# 10-Buffer.net
KiCad netlist of a schematic drawn in Altium Designer
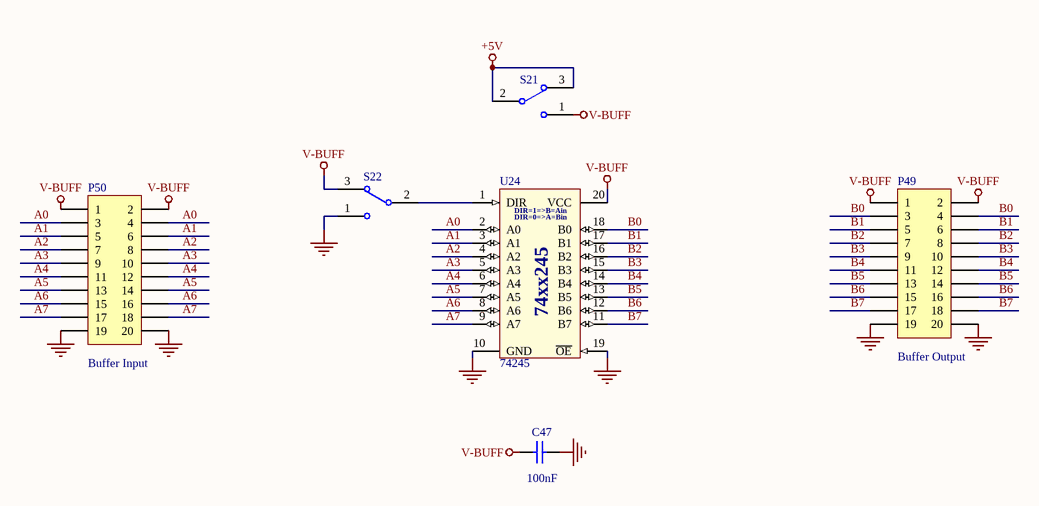
[diagram p0: 10-Buffer.SchDoc]

(export (version "E")
  (design (tool "Eeschema 10.0.6"))
  (components
    (comp (ref "C47")
      (value "100nF")
      (footprint "C-0805")
      (description "Capacitor")
      (fields (field (name "Comment") "104") (field (name "PUBLISHER") "Altium Limited"))
      (libsource (lib "Miscellaneous Devices") (part "Cap"))
    )
    (comp (ref "P49")
      (value "Buffer Output")
      (footprint "HDR2X10")
      (description "Header, 10-Pin, Dual row")
      (fields (field (name "Comment") "H10X2"))
      (libsource (lib "Miscellaneous Connectors") (part "Header 10X2"))
    )
    (comp (ref "P50")
      (value "Buffer Input")
      (footprint "HDR2X10")
      (description "Header, 10-Pin, Dual row")
      (fields (field (name "Comment") "H10X2"))
      (libsource (lib "Miscellaneous Connectors") (part "Header 10X2"))
    )
    (comp (ref "S21")
      (value "SW-SPDT")
      (footprint "SW-DIP1SMD")
      (description "SPDT Subminiature Toggle Switch, Right Angle Mounting, Vertical Actuation")
      (fields (field (name "PUBLISHER") "Altium Limited"))
      (libsource (lib "Miscellaneous Devices") (part "SW-SPDT"))
    )
    (comp (ref "S22")
      (value "SW-SPDT")
      (footprint "SW-DIP1SMD")
      (description "SPDT Subminiature Toggle Switch, Right Angle Mounting, Vertical Actuation")
      (fields (field (name "PUBLISHER") "Altium Limited"))
      (libsource (lib "Miscellaneous Devices") (part "SW-SPDT"))
    )
    (comp (ref "U24")
      (value "74245")
      (footprint "DIP20/W0.3")
      (description "Octal bus tranceiver; 3-state")
      (fields (field (name "COPYRIGHT BY") "VanDungEvn@gmail.com"))
      (libsource (lib "nhoccon1") (part "74245"))
    )
  )
  (nets
    (net (code "1") (name "+5V") (class "Default")
      (node (ref "S21") (pin "2") (pinfunction "2_2") (pintype "passive"))
      (node (ref "S21") (pin "3") (pinfunction "3_3") (pintype "passive"))
    )
    (net (code "2") (name "/A0") (class "Default")
      (node (ref "P50") (pin "3") (pinfunction "3_3") (pintype "passive"))
      (node (ref "P50") (pin "4") (pinfunction "4_4") (pintype "passive"))
      (node (ref "U24") (pin "2") (pinfunction "A0_2") (pintype "bidirectional"))
    )
    (net (code "3") (name "/A1") (class "Default")
      (node (ref "P50") (pin "5") (pinfunction "5_5") (pintype "passive"))
      (node (ref "P50") (pin "6") (pinfunction "6_6") (pintype "passive"))
      (node (ref "U24") (pin "3") (pinfunction "A1_3") (pintype "bidirectional"))
    )
    (net (code "4") (name "/A2") (class "Default")
      (node (ref "P50") (pin "7") (pinfunction "7_7") (pintype "passive"))
      (node (ref "P50") (pin "8") (pinfunction "8_8") (pintype "passive"))
      (node (ref "U24") (pin "4") (pinfunction "A2_4") (pintype "bidirectional"))
    )
    (net (code "5") (name "/A3") (class "Default")
      (node (ref "P50") (pin "10") (pinfunction "10_10") (pintype "passive"))
      (node (ref "P50") (pin "9") (pinfunction "9_9") (pintype "passive"))
      (node (ref "U24") (pin "5") (pinfunction "A3_5") (pintype "bidirectional"))
    )
    (net (code "6") (name "/A4") (class "Default")
      (node (ref "P50") (pin "11") (pinfunction "11_11") (pintype "passive"))
      (node (ref "P50") (pin "12") (pinfunction "12_12") (pintype "passive"))
      (node (ref "U24") (pin "6") (pinfunction "A4_6") (pintype "bidirectional"))
    )
    (net (code "7") (name "/A5") (class "Default")
      (node (ref "P50") (pin "13") (pinfunction "13_13") (pintype "passive"))
      (node (ref "P50") (pin "14") (pinfunction "14_14") (pintype "passive"))
      (node (ref "U24") (pin "7") (pinfunction "A5_7") (pintype "bidirectional"))
    )
    (net (code "8") (name "/A6") (class "Default")
      (node (ref "P50") (pin "15") (pinfunction "15_15") (pintype "passive"))
      (node (ref "P50") (pin "16") (pinfunction "16_16") (pintype "passive"))
      (node (ref "U24") (pin "8") (pinfunction "A6_8") (pintype "bidirectional"))
    )
    (net (code "9") (name "/A7") (class "Default")
      (node (ref "P50") (pin "17") (pinfunction "17_17") (pintype "passive"))
      (node (ref "P50") (pin "18") (pinfunction "18_18") (pintype "passive"))
      (node (ref "U24") (pin "9") (pinfunction "A7_9") (pintype "bidirectional"))
    )
    (net (code "10") (name "/B0") (class "Default")
      (node (ref "P49") (pin "3") (pinfunction "3_3") (pintype "passive"))
      (node (ref "P49") (pin "4") (pinfunction "4_4") (pintype "passive"))
      (node (ref "U24") (pin "18") (pinfunction "B0_18") (pintype "bidirectional"))
    )
    (net (code "11") (name "/B1") (class "Default")
      (node (ref "P49") (pin "5") (pinfunction "5_5") (pintype "passive"))
      (node (ref "P49") (pin "6") (pinfunction "6_6") (pintype "passive"))
      (node (ref "U24") (pin "17") (pinfunction "B1_17") (pintype "bidirectional"))
    )
    (net (code "12") (name "/B2") (class "Default")
      (node (ref "P49") (pin "7") (pinfunction "7_7") (pintype "passive"))
      (node (ref "P49") (pin "8") (pinfunction "8_8") (pintype "passive"))
      (node (ref "U24") (pin "16") (pinfunction "B2_16") (pintype "bidirectional"))
    )
    (net (code "13") (name "/B3") (class "Default")
      (node (ref "P49") (pin "10") (pinfunction "10_10") (pintype "passive"))
      (node (ref "P49") (pin "9") (pinfunction "9_9") (pintype "passive"))
      (node (ref "U24") (pin "15") (pinfunction "B3_15") (pintype "bidirectional"))
    )
    (net (code "14") (name "/B4") (class "Default")
      (node (ref "P49") (pin "11") (pinfunction "11_11") (pintype "passive"))
      (node (ref "P49") (pin "12") (pinfunction "12_12") (pintype "passive"))
      (node (ref "U24") (pin "14") (pinfunction "B4_14") (pintype "bidirectional"))
    )
    (net (code "15") (name "/B5") (class "Default")
      (node (ref "P49") (pin "13") (pinfunction "13_13") (pintype "passive"))
      (node (ref "P49") (pin "14") (pinfunction "14_14") (pintype "passive"))
      (node (ref "U24") (pin "13") (pinfunction "B5_13") (pintype "bidirectional"))
    )
    (net (code "16") (name "/B6") (class "Default")
      (node (ref "P49") (pin "15") (pinfunction "15_15") (pintype "passive"))
      (node (ref "P49") (pin "16") (pinfunction "16_16") (pintype "passive"))
      (node (ref "U24") (pin "12") (pinfunction "B6_12") (pintype "bidirectional"))
    )
    (net (code "17") (name "/B7") (class "Default")
      (node (ref "P49") (pin "17") (pinfunction "17_17") (pintype "passive"))
      (node (ref "P49") (pin "18") (pinfunction "18_18") (pintype "passive"))
      (node (ref "U24") (pin "11") (pinfunction "B7_11") (pintype "bidirectional"))
    )
    (net (code "18") (name "GND") (class "Default")
      (node (ref "C47") (pin "2") (pinfunction "2_2") (pintype "passive"))
      (node (ref "P49") (pin "19") (pinfunction "19_19") (pintype "passive"))
      (node (ref "P49") (pin "20") (pinfunction "20_20") (pintype "passive"))
      (node (ref "P50") (pin "19") (pinfunction "19_19") (pintype "passive"))
      (node (ref "P50") (pin "20") (pinfunction "20_20") (pintype "passive"))
      (node (ref "S22") (pin "1") (pinfunction "1_1") (pintype "passive"))
      (node (ref "U24") (pin "10") (pinfunction "GND_10") (pintype "power_in"))
      (node (ref "U24") (pin "19") (pinfunction "~{OE}_19") (pintype "input"))
    )
    (net (code "19") (name "Net-(U24-DIR)") (class "Default")
      (node (ref "S22") (pin "2") (pinfunction "2_2") (pintype "passive"))
      (node (ref "U24") (pin "1") (pinfunction "DIR_1") (pintype "input"))
    )
    (net (code "20") (name "V-BUFF") (class "Default")
      (node (ref "C47") (pin "1") (pinfunction "1_1") (pintype "passive"))
      (node (ref "P49") (pin "1") (pinfunction "1_1") (pintype "passive"))
      (node (ref "P49") (pin "2") (pinfunction "2_2") (pintype "passive"))
      (node (ref "P50") (pin "1") (pinfunction "1_1") (pintype "passive"))
      (node (ref "P50") (pin "2") (pinfunction "2_2") (pintype "passive"))
      (node (ref "S21") (pin "1") (pinfunction "1_1") (pintype "passive"))
      (node (ref "S22") (pin "3") (pinfunction "3_3") (pintype "passive"))
      (node (ref "U24") (pin "20") (pinfunction "VCC_20") (pintype "power_in"))
    )
  )
)
